# Sheet1.net
KiCad netlist of a schematic drawn in Altium Designer
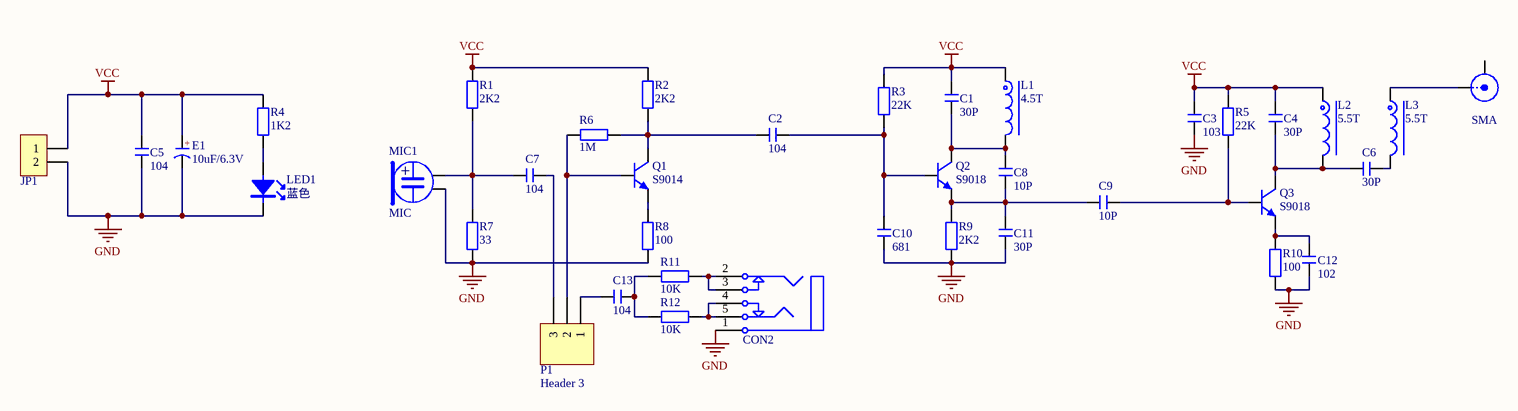
[diagram p0: Sheet1.SchDoc]

(export (version "E")
  (design (tool "Eeschema 10.0.6"))
  (components
    (comp (ref "C1")
      (value "30P")
      (footprint "C 0805_M")
      (description "贴片电容")
      (libsource (lib "01 - 电容-电阻-电感") (part "C"))
    )
    (comp (ref "C2")
      (value "104")
      (footprint "C 0805_M")
      (description "贴片电容")
      (libsource (lib "01 - 电容-电阻-电感") (part "C"))
    )
    (comp (ref "C3")
      (value "103")
      (footprint "C 0805_M")
      (description "贴片电容")
      (libsource (lib "01 - 电容-电阻-电感") (part "C"))
    )
    (comp (ref "C4")
      (value "30P")
      (footprint "C 0805_M")
      (description "贴片电容")
      (libsource (lib "01 - 电容-电阻-电感") (part "C"))
    )
    (comp (ref "C5")
      (value "104")
      (footprint "C 0805_M")
      (description "贴片电容")
      (libsource (lib "01 - 电容-电阻-电感") (part "C"))
    )
    (comp (ref "C6")
      (value "30P")
      (footprint "C 0805_M")
      (description "贴片电容")
      (libsource (lib "01 - 电容-电阻-电感") (part "C"))
    )
    (comp (ref "C7")
      (value "104")
      (footprint "C 0805_M")
      (description "贴片电容")
      (libsource (lib "01 - 电容-电阻-电感") (part "C"))
    )
    (comp (ref "C8")
      (value "10P")
      (footprint "C 0805_M")
      (description "贴片电容")
      (libsource (lib "01 - 电容-电阻-电感") (part "C"))
    )
    (comp (ref "C9")
      (value "10P")
      (footprint "C 0805_M")
      (description "贴片电容")
      (libsource (lib "01 - 电容-电阻-电感") (part "C"))
    )
    (comp (ref "C10")
      (value "681")
      (footprint "C 0805_M")
      (description "贴片电容")
      (libsource (lib "01 - 电容-电阻-电感") (part "C"))
    )
    (comp (ref "C11")
      (value "30P")
      (footprint "C 0805_M")
      (description "贴片电容")
      (libsource (lib "01 - 电容-电阻-电感") (part "C"))
    )
    (comp (ref "C12")
      (value "102")
      (footprint "C 0805_M")
      (description "贴片电容")
      (libsource (lib "01 - 电容-电阻-电感") (part "C"))
    )
    (comp (ref "C13")
      (value "104")
      (footprint "C 0805_M")
      (description "贴片电容")
      (libsource (lib "01 - 电容-电阻-电感") (part "C"))
    )
    (comp (ref "CON1")
      (value "SMA")
      (footprint "RCA RJ-255")
      (description "RCA莲花头AV座")
      (libsource (lib "04 - 接口类-USB接口-网口") (part "SMA"))
    )
    (comp (ref "CON2")
      (value "3F07_BK")
      (footprint "3F07_PK")
      (description "3.5mm耳机插座")
      (libsource (lib "04 - 接口类-USB接口-网口") (part "3F07"))
    )
    (comp (ref "E1")
      (value "10uF/6.3V")
      (footprint "CD C(6032)")
      (description "贴片钽电容")
      (libsource (lib "01 - 电容-电阻-电感") (part "CT"))
    )
    (comp (ref "JP1")
      (value "HDR-1X2")
      (footprint "KF2EDGK5.0-LI-2P")
      (description "2P接插件")
      (libsource (lib "21 - 接插件-脚距5.0mm") (part "Header 2"))
    )
    (comp (ref "L1")
      (value "4.5T")
      (footprint "L")
      (description "工字电感")
      (libsource (lib "01 - 电容-电阻-电感") (part "L-PK"))
    )
    (comp (ref "L2")
      (value "5.5T")
      (footprint "L")
      (description "工字电感")
      (libsource (lib "01 - 电容-电阻-电感") (part "L-PK"))
    )
    (comp (ref "L3")
      (value "5.5T")
      (footprint "L")
      (description "工字电感")
      (libsource (lib "01 - 电容-电阻-电感") (part "L-PK"))
    )
    (comp (ref "LED1")
      (value "蓝色")
      (footprint "LED 0805B")
      (description "贴片LED")
      (libsource (lib "02 - 二极管(LED)-三极管-整流桥") (part "LED-SMD"))
    )
    (comp (ref "MIC1")
      (value "MIC")
      (footprint "MIC-6*5.5mm")
      (description "电容麦克风")
      (libsource (lib "09 - 各种传感器(传感元器件)") (part "MIC"))
    )
    (comp (ref "P1")
      (value "Header 3")
      (footprint "HDR1X3")
      (description "Header, 3-Pin")
      (fields (field (name "PUBLISHER") "Altium Limited"))
      (libsource (lib "Miscellaneous Connectors") (part "Header 3"))
    )
    (comp (ref "Q1")
      (value "S9014")
      (footprint "SOT23-3M")
      (description "低噪放大-NPN型")
      (libsource (lib "02 - 二极管(LED)-三极管-整流桥") (part "9014-SMD"))
    )
    (comp (ref "Q2")
      (value "S9018")
      (footprint "SOT23-3M")
      (description "低噪放大-NPN型")
      (libsource (lib "02 - 二极管(LED)-三极管-整流桥") (part "9014-SMD"))
    )
    (comp (ref "Q3")
      (value "S9018")
      (footprint "SOT23-3M")
      (description "低噪放大-NPN型")
      (libsource (lib "02 - 二极管(LED)-三极管-整流桥") (part "9014-SMD"))
    )
    (comp (ref "R1")
      (value "2K2")
      (footprint "R 0805_M")
      (description "贴片电阻")
      (libsource (lib "01 - 电容-电阻-电感") (part "R"))
    )
    (comp (ref "R2")
      (value "2K2")
      (footprint "R 0805_M")
      (description "贴片电阻")
      (libsource (lib "01 - 电容-电阻-电感") (part "R"))
    )
    (comp (ref "R3")
      (value "22K")
      (footprint "R 0805_M")
      (description "贴片电阻")
      (libsource (lib "01 - 电容-电阻-电感") (part "R"))
    )
    (comp (ref "R4")
      (value "1K2")
      (footprint "R 0805_M")
      (description "贴片电阻")
      (libsource (lib "01 - 电容-电阻-电感") (part "R"))
    )
    (comp (ref "R5")
      (value "22K")
      (footprint "R 0805_M")
      (description "贴片电阻")
      (libsource (lib "01 - 电容-电阻-电感") (part "R"))
    )
    (comp (ref "R6")
      (value "1M")
      (footprint "R 0805_M")
      (description "贴片电阻")
      (libsource (lib "01 - 电容-电阻-电感") (part "R"))
    )
    (comp (ref "R7")
      (value "33")
      (footprint "R 0805_M")
      (description "贴片电阻")
      (libsource (lib "01 - 电容-电阻-电感") (part "R"))
    )
    (comp (ref "R8")
      (value "100")
      (footprint "R 0805_M")
      (description "贴片电阻")
      (libsource (lib "01 - 电容-电阻-电感") (part "R"))
    )
    (comp (ref "R9")
      (value "2K2")
      (footprint "R 0805_M")
      (description "贴片电阻")
      (libsource (lib "01 - 电容-电阻-电感") (part "R"))
    )
    (comp (ref "R10")
      (value "100")
      (footprint "R 0805_M")
      (description "贴片电阻")
      (libsource (lib "01 - 电容-电阻-电感") (part "R"))
    )
    (comp (ref "R11")
      (value "10K")
      (footprint "R 0805_M")
      (description "贴片电阻")
      (libsource (lib "01 - 电容-电阻-电感") (part "R"))
    )
    (comp (ref "R12")
      (value "10K")
      (footprint "R 0805_M")
      (description "贴片电阻")
      (libsource (lib "01 - 电容-电阻-电感") (part "R"))
    )
  )
  (nets
    (net (code "1") (name "GND") (class "Default")
      (node (ref "C10") (pin "2") (pinfunction "2_2") (pintype "passive"))
      (node (ref "C11") (pin "2") (pinfunction "2_2") (pintype "passive"))
      (node (ref "C12") (pin "2") (pinfunction "2_2") (pintype "passive"))
      (node (ref "C3") (pin "2") (pinfunction "2_2") (pintype "passive"))
      (node (ref "C5") (pin "1") (pinfunction "1_1") (pintype "passive"))
      (node (ref "CON2") (pin "1") (pinfunction "1_1") (pintype "passive"))
      (node (ref "E1") (pin "2") (pinfunction "K_2") (pintype "passive"))
      (node (ref "JP1") (pin "2") (pinfunction "2_2") (pintype "passive"))
      (node (ref "LED1") (pin "2") (pinfunction "K_2") (pintype "passive"))
      (node (ref "MIC1") (pin "2") (pinfunction "2_2") (pintype "passive"))
      (node (ref "R10") (pin "1") (pinfunction "1_1") (pintype "passive"))
      (node (ref "R7") (pin "1") (pinfunction "1_1") (pintype "passive"))
      (node (ref "R8") (pin "1") (pinfunction "1_1") (pintype "passive"))
      (node (ref "R9") (pin "1") (pinfunction "1_1") (pintype "passive"))
    )
    (net (code "2") (name "Net-(C6-Pad2)") (class "Default")
      (node (ref "C6") (pin "2") (pinfunction "2_2") (pintype "passive"))
      (node (ref "L3") (pin "2") (pinfunction "2_2") (pintype "passive"))
    )
    (net (code "3") (name "Net-(C7-Pad1)") (class "Default")
      (node (ref "C7") (pin "1") (pinfunction "1_1") (pintype "passive"))
      (node (ref "P1") (pin "3") (pinfunction "3_3") (pintype "passive"))
    )
    (net (code "4") (name "Net-(C7-Pad2)") (class "Default")
      (node (ref "C7") (pin "2") (pinfunction "2_2") (pintype "passive"))
      (node (ref "MIC1") (pin "1") (pinfunction "1_1") (pintype "passive"))
      (node (ref "R1") (pin "1") (pinfunction "1_1") (pintype "passive"))
      (node (ref "R7") (pin "2") (pinfunction "2_2") (pintype "passive"))
    )
    (net (code "5") (name "Net-(C13-Pad1)") (class "Default")
      (node (ref "C13") (pin "1") (pinfunction "1_1") (pintype "passive"))
      (node (ref "P1") (pin "1") (pinfunction "1_1") (pintype "passive"))
    )
    (net (code "6") (name "Net-(C13-Pad2)") (class "Default")
      (node (ref "C13") (pin "2") (pinfunction "2_2") (pintype "passive"))
      (node (ref "R11") (pin "1") (pinfunction "1_1") (pintype "passive"))
      (node (ref "R12") (pin "1") (pinfunction "1_1") (pintype "passive"))
    )
    (net (code "7") (name "Net-(CON1-X)") (class "Default")
      (node (ref "CON1") (pin "1") (pinfunction "X_1") (pintype "passive"))
      (node (ref "L3") (pin "1") (pinfunction "1_1") (pintype "passive"))
    )
    (net (code "8") (name "Net-(CON2-Pad2)") (class "Default")
      (node (ref "CON2") (pin "2") (pinfunction "2_2") (pintype "passive"))
      (node (ref "CON2") (pin "3") (pinfunction "3_3") (pintype "passive"))
      (node (ref "R11") (pin "2") (pinfunction "2_2") (pintype "passive"))
    )
    (net (code "9") (name "Net-(CON2-Pad4)") (class "Default")
      (node (ref "CON2") (pin "4") (pinfunction "4_4") (pintype "passive"))
      (node (ref "CON2") (pin "5") (pinfunction "5_5") (pintype "passive"))
      (node (ref "R12") (pin "2") (pinfunction "2_2") (pintype "passive"))
    )
    (net (code "10") (name "Net-(LED1-A)") (class "Default")
      (node (ref "LED1") (pin "1") (pinfunction "A_1") (pintype "passive"))
      (node (ref "R4") (pin "1") (pinfunction "1_1") (pintype "passive"))
    )
    (net (code "11") (name "Net-(Q1-B)") (class "Default")
      (node (ref "P1") (pin "2") (pinfunction "2_2") (pintype "passive"))
      (node (ref "Q1") (pin "1") (pinfunction "B_1") (pintype "passive"))
      (node (ref "R6") (pin "2") (pinfunction "2_2") (pintype "passive"))
    )
    (net (code "12") (name "Net-(Q1-C)") (class "Default")
      (node (ref "C2") (pin "2") (pinfunction "2_2") (pintype "passive"))
      (node (ref "Q1") (pin "3") (pinfunction "C_3") (pintype "passive"))
      (node (ref "R2") (pin "1") (pinfunction "1_1") (pintype "passive"))
      (node (ref "R6") (pin "1") (pinfunction "1_1") (pintype "passive"))
    )
    (net (code "13") (name "Net-(Q1-E)") (class "Default")
      (node (ref "Q1") (pin "2") (pinfunction "E_2") (pintype "passive"))
      (node (ref "R8") (pin "2") (pinfunction "2_2") (pintype "passive"))
    )
    (net (code "14") (name "Net-(Q2-B)") (class "Default")
      (node (ref "C10") (pin "1") (pinfunction "1_1") (pintype "passive"))
      (node (ref "C2") (pin "1") (pinfunction "1_1") (pintype "passive"))
      (node (ref "Q2") (pin "1") (pinfunction "B_1") (pintype "passive"))
      (node (ref "R3") (pin "1") (pinfunction "1_1") (pintype "passive"))
    )
    (net (code "15") (name "Net-(Q2-C)") (class "Default")
      (node (ref "C1") (pin "2") (pinfunction "2_2") (pintype "passive"))
      (node (ref "C8") (pin "1") (pinfunction "1_1") (pintype "passive"))
      (node (ref "L1") (pin "2") (pinfunction "2_2") (pintype "passive"))
      (node (ref "Q2") (pin "3") (pinfunction "C_3") (pintype "passive"))
    )
    (net (code "16") (name "Net-(Q2-E)") (class "Default")
      (node (ref "C11") (pin "1") (pinfunction "1_1") (pintype "passive"))
      (node (ref "C8") (pin "2") (pinfunction "2_2") (pintype "passive"))
      (node (ref "C9") (pin "1") (pinfunction "1_1") (pintype "passive"))
      (node (ref "Q2") (pin "2") (pinfunction "E_2") (pintype "passive"))
      (node (ref "R9") (pin "2") (pinfunction "2_2") (pintype "passive"))
    )
    (net (code "17") (name "Net-(Q3-B)") (class "Default")
      (node (ref "C9") (pin "2") (pinfunction "2_2") (pintype "passive"))
      (node (ref "Q3") (pin "1") (pinfunction "B_1") (pintype "passive"))
      (node (ref "R5") (pin "1") (pinfunction "1_1") (pintype "passive"))
    )
    (net (code "18") (name "Net-(Q3-C)") (class "Default")
      (node (ref "C4") (pin "2") (pinfunction "2_2") (pintype "passive"))
      (node (ref "C6") (pin "1") (pinfunction "1_1") (pintype "passive"))
      (node (ref "L2") (pin "2") (pinfunction "2_2") (pintype "passive"))
      (node (ref "Q3") (pin "3") (pinfunction "C_3") (pintype "passive"))
    )
    (net (code "19") (name "Net-(Q3-E)") (class "Default")
      (node (ref "C12") (pin "1") (pinfunction "1_1") (pintype "passive"))
      (node (ref "Q3") (pin "2") (pinfunction "E_2") (pintype "passive"))
      (node (ref "R10") (pin "2") (pinfunction "2_2") (pintype "passive"))
    )
    (net (code "20") (name "VCC") (class "Default")
      (node (ref "C1") (pin "1") (pinfunction "1_1") (pintype "passive"))
      (node (ref "C3") (pin "1") (pinfunction "1_1") (pintype "passive"))
      (node (ref "C4") (pin "1") (pinfunction "1_1") (pintype "passive"))
      (node (ref "C5") (pin "2") (pinfunction "2_2") (pintype "passive"))
      (node (ref "E1") (pin "1") (pinfunction "A_1") (pintype "passive"))
      (node (ref "JP1") (pin "1") (pinfunction "1_1") (pintype "passive"))
      (node (ref "L1") (pin "1") (pinfunction "1_1") (pintype "passive"))
      (node (ref "L2") (pin "1") (pinfunction "1_1") (pintype "passive"))
      (node (ref "R1") (pin "2") (pinfunction "2_2") (pintype "passive"))
      (node (ref "R2") (pin "2") (pinfunction "2_2") (pintype "passive"))
      (node (ref "R3") (pin "2") (pinfunction "2_2") (pintype "passive"))
      (node (ref "R4") (pin "2") (pinfunction "2_2") (pintype "passive"))
      (node (ref "R5") (pin "2") (pinfunction "2_2") (pintype "passive"))
    )
    (net (code "21") (name "unconnected-(CON1-Y-Pad2)") (class "Default")
      (node (ref "CON1") (pin "2") (pinfunction "Y_2") (pintype "passive"))
    )
  )
)
